# Placa_Principal_-_mar_o_2018.net
KiCad netlist of a schematic drawn in EAGLE
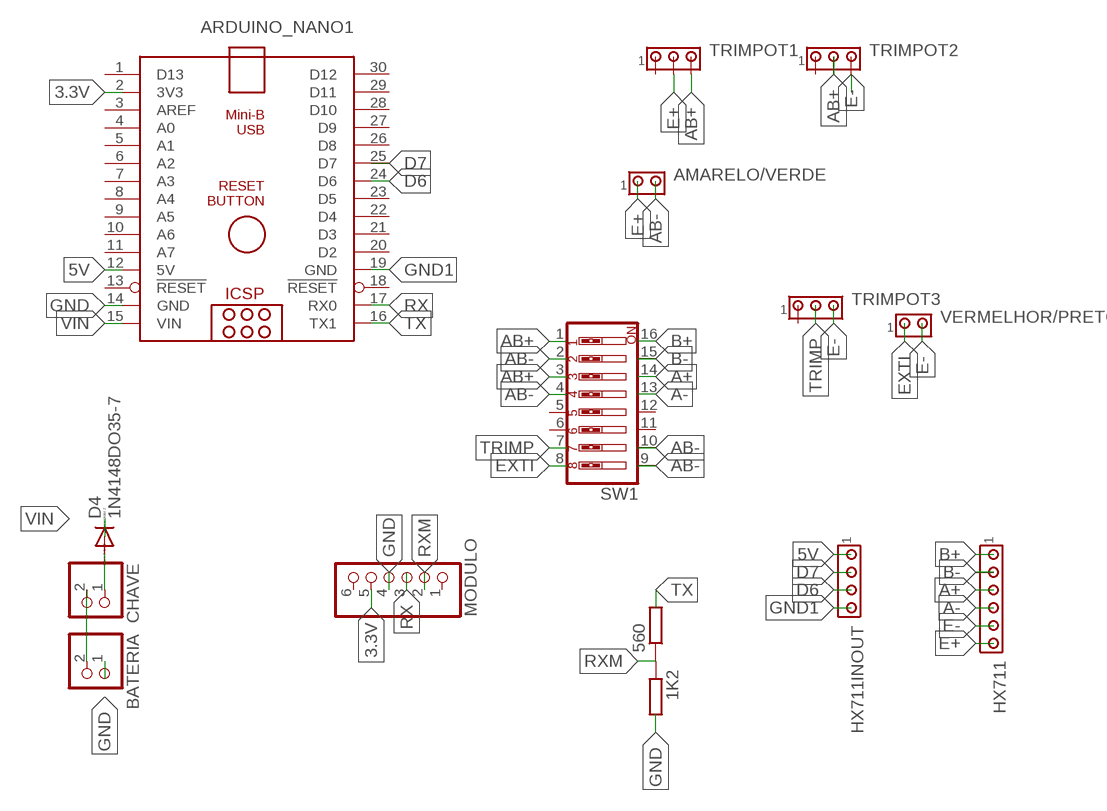
[diagram p0: schematic, sheet 1]

(export (version "E")
  (design (tool "Eeschema 10.0.6"))
  (components
    (comp (ref "1K2")
      (value "R-EU_0204/5")
      (footprint "eagle-import:0204_5")
      (libsource (lib "eagle-import") (part "R-EU_0204/5"))
    )
    (comp (ref "560")
      (value "R-EU_0204/5")
      (footprint "eagle-import:0204_5")
      (libsource (lib "eagle-import") (part "R-EU_0204/5"))
    )
    (comp (ref "AMARELO/VERDE")
      (value "MTA02-100")
      (footprint "eagle-import:10X02MTA")
      (libsource (lib "eagle-import") (part "MTA02-100"))
    )
    (comp (ref "ARDUINO_NANO1")
      (value "ARDUINO_NANO")
      (footprint "eagle-import:ARDUINO_NANO")
      (libsource (lib "eagle-import") (part "ARDUINO_NANO"))
    )
    (comp (ref "BATERIA")
      (value "PINHD-1X2")
      (footprint "eagle-import:1X02")
      (libsource (lib "eagle-import") (part "PINHD-1X2"))
    )
    (comp (ref "CHAVE")
      (value "PINHD-1X2")
      (footprint "eagle-import:1X02")
      (libsource (lib "eagle-import") (part "PINHD-1X2"))
    )
    (comp (ref "D4")
      (value "1N4148DO35-7")
      (footprint "eagle-import:DO35-7")
      (libsource (lib "eagle-import") (part "1N4148DO35-7"))
    )
    (comp (ref "HX711")
      (value "MTA06-100")
      (footprint "eagle-import:10X06MTA")
      (libsource (lib "eagle-import") (part "MTA06-100"))
    )
    (comp (ref "HX711INOUT")
      (value "MTA04-100")
      (footprint "eagle-import:10X04MTA")
      (libsource (lib "eagle-import") (part "MTA04-100"))
    )
    (comp (ref "MODULO")
      (value "PINHD-1X6")
      (footprint "eagle-import:1X06")
      (libsource (lib "eagle-import") (part "PINHD-1X6"))
    )
    (comp (ref "SW1")
      (value "SW_DIP-8")
      (footprint "eagle-import:EDG-08")
      (libsource (lib "eagle-import") (part "SW_DIP-8"))
    )
    (comp (ref "TRIMPOT1")
      (value "MTA03-100")
      (footprint "eagle-import:10X03MTA")
      (libsource (lib "eagle-import") (part "MTA03-100"))
    )
    (comp (ref "TRIMPOT2")
      (value "MTA03-100")
      (footprint "eagle-import:10X03MTA")
      (libsource (lib "eagle-import") (part "MTA03-100"))
    )
    (comp (ref "TRIMPOT3")
      (value "MTA03-100")
      (footprint "eagle-import:10X03MTA")
      (libsource (lib "eagle-import") (part "MTA03-100"))
    )
    (comp (ref "VERMELHOR/PRETO")
      (value "MTA02-100")
      (footprint "eagle-import:10X02MTA")
      (libsource (lib "eagle-import") (part "MTA02-100"))
    )
  )
  (nets
    (net (code "1") (name "3.3V") (class "Default")
      (node (ref "ARDUINO_NANO1") (pin "2") (pinfunction "3V3_2") (pintype "output"))
      (node (ref "MODULO") (pin "5") (pinfunction "5_5") (pintype "passive"))
    )
    (net (code "2") (name "5V") (class "Default")
      (node (ref "ARDUINO_NANO1") (pin "12") (pinfunction "5V_12") (pintype "power_in"))
      (node (ref "HX711INOUT") (pin "1") (pinfunction "1_1") (pintype "passive"))
    )
    (net (code "3") (name "A+") (class "Default")
      (node (ref "HX711") (pin "3") (pinfunction "3_3") (pintype "passive"))
      (node (ref "SW1") (pin "14") (pinfunction "14_14") (pintype "passive"))
    )
    (net (code "4") (name "A-") (class "Default")
      (node (ref "HX711") (pin "4") (pinfunction "4_4") (pintype "passive"))
      (node (ref "SW1") (pin "13") (pinfunction "13_13") (pintype "passive"))
    )
    (net (code "5") (name "AB+") (class "Default")
      (node (ref "SW1") (pin "1") (pinfunction "1_1") (pintype "passive"))
      (node (ref "SW1") (pin "3") (pinfunction "3_3") (pintype "passive"))
      (node (ref "TRIMPOT1") (pin "3") (pinfunction "3_3") (pintype "passive"))
      (node (ref "TRIMPOT2") (pin "2") (pinfunction "2_2") (pintype "passive"))
    )
    (net (code "6") (name "AB-") (class "Default")
      (node (ref "AMARELO/VERDE") (pin "2") (pinfunction "2_2") (pintype "passive"))
      (node (ref "SW1") (pin "10") (pinfunction "10_10") (pintype "passive"))
      (node (ref "SW1") (pin "2") (pinfunction "2_2") (pintype "passive"))
      (node (ref "SW1") (pin "4") (pinfunction "4_4") (pintype "passive"))
      (node (ref "SW1") (pin "9") (pinfunction "9_9") (pintype "passive"))
    )
    (net (code "7") (name "B+") (class "Default")
      (node (ref "HX711") (pin "1") (pinfunction "1_1") (pintype "passive"))
      (node (ref "SW1") (pin "16") (pinfunction "16_16") (pintype "passive"))
    )
    (net (code "8") (name "B-") (class "Default")
      (node (ref "HX711") (pin "2") (pinfunction "2_2") (pintype "passive"))
      (node (ref "SW1") (pin "15") (pinfunction "15_15") (pintype "passive"))
    )
    (net (code "9") (name "D6") (class "Default")
      (node (ref "ARDUINO_NANO1") (pin "24") (pinfunction "D6_24") (pintype "bidirectional"))
      (node (ref "HX711INOUT") (pin "3") (pinfunction "3_3") (pintype "passive"))
    )
    (net (code "10") (name "D7") (class "Default")
      (node (ref "ARDUINO_NANO1") (pin "25") (pinfunction "D7_25") (pintype "bidirectional"))
      (node (ref "HX711INOUT") (pin "2") (pinfunction "2_2") (pintype "passive"))
    )
    (net (code "11") (name "E+") (class "Default")
      (node (ref "AMARELO/VERDE") (pin "1") (pinfunction "1_1") (pintype "passive"))
      (node (ref "HX711") (pin "6") (pinfunction "6_6") (pintype "passive"))
      (node (ref "TRIMPOT1") (pin "2") (pinfunction "2_2") (pintype "passive"))
    )
    (net (code "12") (name "E-") (class "Default")
      (node (ref "HX711") (pin "5") (pinfunction "5_5") (pintype "passive"))
      (node (ref "TRIMPOT2") (pin "3") (pinfunction "3_3") (pintype "passive"))
      (node (ref "TRIMPOT3") (pin "3") (pinfunction "3_3") (pintype "passive"))
      (node (ref "VERMELHOR/PRETO") (pin "2") (pinfunction "2_2") (pintype "passive"))
    )
    (net (code "13") (name "EXTI") (class "Default")
      (node (ref "SW1") (pin "8") (pinfunction "8_8") (pintype "passive"))
      (node (ref "VERMELHOR/PRETO") (pin "1") (pinfunction "1_1") (pintype "passive"))
    )
    (net (code "14") (name "GND") (class "Default")
      (node (ref "1K2") (pin "2") (pinfunction "2_2") (pintype "passive"))
      (node (ref "ARDUINO_NANO1") (pin "14") (pinfunction "GND_14") (pintype "power_in"))
      (node (ref "BATERIA") (pin "1") (pinfunction "1_1") (pintype "passive"))
      (node (ref "MODULO") (pin "4") (pinfunction "4_4") (pintype "passive"))
    )
    (net (code "15") (name "GND1") (class "Default")
      (node (ref "ARDUINO_NANO1") (pin "19") (pinfunction "GND_19") (pintype "power_in"))
      (node (ref "HX711INOUT") (pin "4") (pinfunction "4_4") (pintype "passive"))
    )
    (net (code "16") (name "Net-(BATERIA-Pad2)") (class "Default")
      (node (ref "BATERIA") (pin "2") (pinfunction "2_2") (pintype "passive"))
      (node (ref "CHAVE") (pin "2") (pinfunction "2_2") (pintype "passive"))
    )
    (net (code "17") (name "Net-(CHAVE-Pad1)") (class "Default")
      (node (ref "CHAVE") (pin "1") (pinfunction "1_1") (pintype "passive"))
      (node (ref "D4") (pin "A") (pinfunction "A_A") (pintype "passive"))
    )
    (net (code "18") (name "RX") (class "Default")
      (node (ref "ARDUINO_NANO1") (pin "17") (pinfunction "RX0_17") (pintype "bidirectional"))
      (node (ref "MODULO") (pin "3") (pinfunction "3_3") (pintype "passive"))
    )
    (net (code "19") (name "RXM") (class "Default")
      (node (ref "1K2") (pin "1") (pinfunction "1_1") (pintype "passive"))
      (node (ref "560") (pin "1") (pinfunction "1_1") (pintype "passive"))
      (node (ref "MODULO") (pin "2") (pinfunction "2_2") (pintype "passive"))
    )
    (net (code "20") (name "TRIMP") (class "Default")
      (node (ref "SW1") (pin "7") (pinfunction "7_7") (pintype "passive"))
      (node (ref "TRIMPOT3") (pin "2") (pinfunction "2_2") (pintype "passive"))
    )
    (net (code "21") (name "TX") (class "Default")
      (node (ref "560") (pin "2") (pinfunction "2_2") (pintype "passive"))
      (node (ref "ARDUINO_NANO1") (pin "16") (pinfunction "TX1_16") (pintype "bidirectional"))
    )
    (net (code "22") (name "VIN") (class "Default")
      (node (ref "ARDUINO_NANO1") (pin "15") (pinfunction "VIN_15") (pintype "power_in"))
      (node (ref "D4") (pin "C") (pinfunction "C_C") (pintype "passive"))
    )
    (net (code "23") (name "unconnected-(ARDUINO_NANO1-A0-Pad4)") (class "Default")
      (node (ref "ARDUINO_NANO1") (pin "4") (pinfunction "A0_4") (pintype "bidirectional"))
    )
    (net (code "24") (name "unconnected-(ARDUINO_NANO1-A1-Pad5)") (class "Default")
      (node (ref "ARDUINO_NANO1") (pin "5") (pinfunction "A1_5") (pintype "bidirectional"))
    )
    (net (code "25") (name "unconnected-(ARDUINO_NANO1-A2-Pad6)") (class "Default")
      (node (ref "ARDUINO_NANO1") (pin "6") (pinfunction "A2_6") (pintype "bidirectional"))
    )
    (net (code "26") (name "unconnected-(ARDUINO_NANO1-A3-Pad7)") (class "Default")
      (node (ref "ARDUINO_NANO1") (pin "7") (pinfunction "A3_7") (pintype "bidirectional"))
    )
    (net (code "27") (name "unconnected-(ARDUINO_NANO1-A4-Pad8)") (class "Default")
      (node (ref "ARDUINO_NANO1") (pin "8") (pinfunction "A4_8") (pintype "bidirectional"))
    )
    (net (code "28") (name "unconnected-(ARDUINO_NANO1-A5-Pad9)") (class "Default")
      (node (ref "ARDUINO_NANO1") (pin "9") (pinfunction "A5_9") (pintype "bidirectional"))
    )
    (net (code "29") (name "unconnected-(ARDUINO_NANO1-A6-Pad10)") (class "Default")
      (node (ref "ARDUINO_NANO1") (pin "10") (pinfunction "A6_10") (pintype "bidirectional"))
    )
    (net (code "30") (name "unconnected-(ARDUINO_NANO1-A7-Pad11)") (class "Default")
      (node (ref "ARDUINO_NANO1") (pin "11") (pinfunction "A7_11") (pintype "bidirectional"))
    )
    (net (code "31") (name "unconnected-(ARDUINO_NANO1-AREF-Pad3)") (class "Default")
      (node (ref "ARDUINO_NANO1") (pin "3") (pinfunction "AREF_3") (pintype "input"))
    )
    (net (code "32") (name "unconnected-(ARDUINO_NANO1-D2-Pad20)") (class "Default")
      (node (ref "ARDUINO_NANO1") (pin "20") (pinfunction "D2_20") (pintype "bidirectional"))
    )
    (net (code "33") (name "unconnected-(ARDUINO_NANO1-D3-Pad21)") (class "Default")
      (node (ref "ARDUINO_NANO1") (pin "21") (pinfunction "D3_21") (pintype "bidirectional"))
    )
    (net (code "34") (name "unconnected-(ARDUINO_NANO1-D4-Pad22)") (class "Default")
      (node (ref "ARDUINO_NANO1") (pin "22") (pinfunction "D4_22") (pintype "bidirectional"))
    )
    (net (code "35") (name "unconnected-(ARDUINO_NANO1-D5-Pad23)") (class "Default")
      (node (ref "ARDUINO_NANO1") (pin "23") (pinfunction "D5_23") (pintype "bidirectional"))
    )
    (net (code "36") (name "unconnected-(ARDUINO_NANO1-D8-Pad26)") (class "Default")
      (node (ref "ARDUINO_NANO1") (pin "26") (pinfunction "D8_26") (pintype "bidirectional"))
    )
    (net (code "37") (name "unconnected-(ARDUINO_NANO1-D9-Pad27)") (class "Default")
      (node (ref "ARDUINO_NANO1") (pin "27") (pinfunction "D9_27") (pintype "bidirectional"))
    )
    (net (code "38") (name "unconnected-(ARDUINO_NANO1-D10-Pad28)") (class "Default")
      (node (ref "ARDUINO_NANO1") (pin "28") (pinfunction "D10_28") (pintype "bidirectional"))
    )
    (net (code "39") (name "unconnected-(ARDUINO_NANO1-D11-Pad29)") (class "Default")
      (node (ref "ARDUINO_NANO1") (pin "29") (pinfunction "D11_29") (pintype "bidirectional"))
    )
    (net (code "40") (name "unconnected-(ARDUINO_NANO1-D12-Pad30)") (class "Default")
      (node (ref "ARDUINO_NANO1") (pin "30") (pinfunction "D12_30") (pintype "bidirectional"))
    )
    (net (code "41") (name "unconnected-(ARDUINO_NANO1-D13-Pad1)") (class "Default")
      (node (ref "ARDUINO_NANO1") (pin "1") (pinfunction "D13_1") (pintype "bidirectional"))
    )
    (net (code "42") (name "unconnected-(ARDUINO_NANO1-~{RESET}-Pad13)") (class "Default")
      (node (ref "ARDUINO_NANO1") (pin "13") (pinfunction "~{RESET}_13") (pintype "input"))
    )
    (net (code "43") (name "unconnected-(ARDUINO_NANO1-~{RESET}-Pad18)") (class "Default")
      (node (ref "ARDUINO_NANO1") (pin "18") (pinfunction "~{RESET}_18") (pintype "input"))
    )
    (net (code "44") (name "unconnected-(MODULO-Pad1)") (class "Default")
      (node (ref "MODULO") (pin "1") (pinfunction "1_1") (pintype "passive"))
    )
    (net (code "45") (name "unconnected-(MODULO-Pad6)") (class "Default")
      (node (ref "MODULO") (pin "6") (pinfunction "6_6") (pintype "passive"))
    )
    (net (code "46") (name "unconnected-(SW1-Pad5)") (class "Default")
      (node (ref "SW1") (pin "5") (pinfunction "5_5") (pintype "passive"))
    )
    (net (code "47") (name "unconnected-(SW1-Pad6)") (class "Default")
      (node (ref "SW1") (pin "6") (pinfunction "6_6") (pintype "passive"))
    )
    (net (code "48") (name "unconnected-(SW1-Pad11)") (class "Default")
      (node (ref "SW1") (pin "11") (pinfunction "11_11") (pintype "passive"))
    )
    (net (code "49") (name "unconnected-(SW1-Pad12)") (class "Default")
      (node (ref "SW1") (pin "12") (pinfunction "12_12") (pintype "passive"))
    )
    (net (code "50") (name "unconnected-(TRIMPOT1-Pad1)") (class "Default")
      (node (ref "TRIMPOT1") (pin "1") (pinfunction "1_1") (pintype "passive"))
    )
    (net (code "51") (name "unconnected-(TRIMPOT2-Pad1)") (class "Default")
      (node (ref "TRIMPOT2") (pin "1") (pinfunction "1_1") (pintype "passive"))
    )
    (net (code "52") (name "unconnected-(TRIMPOT3-Pad1)") (class "Default")
      (node (ref "TRIMPOT3") (pin "1") (pinfunction "1_1") (pintype "passive"))
    )
  )
)
